# goodthopter10.net
KiCad netlist of a schematic drawn in EAGLE
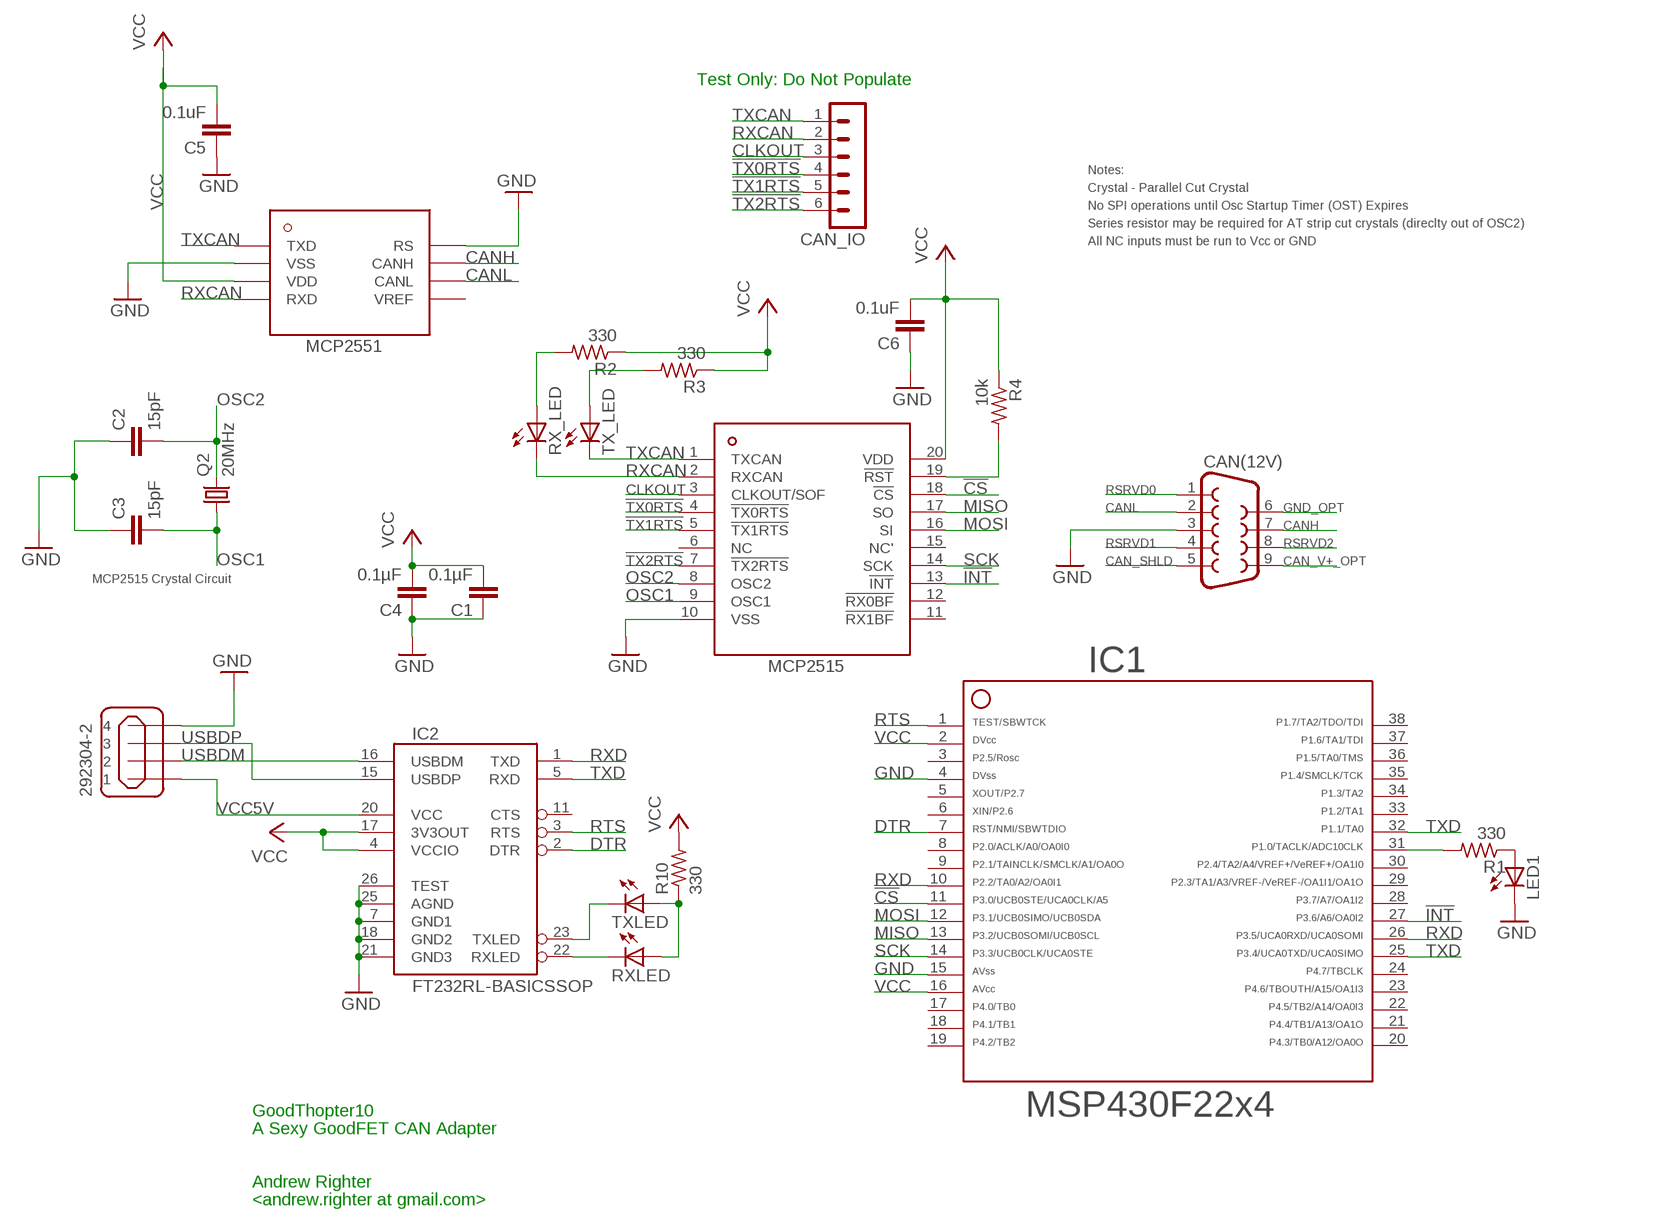
[diagram p0: schematic, sheet 1]

(export (version "E")
  (design (tool "Eeschema 10.0.6"))
  (components
    (comp (ref "292304-2")
      (value "MINI-USB_4P-292304-2")
      (footprint "eagle-import:85-32004-10X")
      (libsource (lib "eagle-import") (part "MINI-USB_4P-292304-2"))
    )
    (comp (ref "C1")
      (value "0.1µF")
      (footprint "eagle-import:C0603")
      (libsource (lib "eagle-import") (part "C-EUC0603"))
    )
    (comp (ref "C2")
      (value "15pF")
      (footprint "eagle-import:C0603")
      (libsource (lib "eagle-import") (part "C-EUC0603"))
    )
    (comp (ref "C3")
      (value "15pF")
      (footprint "eagle-import:C0603")
      (libsource (lib "eagle-import") (part "C-EUC0603"))
    )
    (comp (ref "C4")
      (value "0.1µF")
      (footprint "eagle-import:C0603")
      (libsource (lib "eagle-import") (part "C-EUC0603"))
    )
    (comp (ref "C5")
      (value "0.1uF")
      (footprint "eagle-import:C0603")
      (libsource (lib "eagle-import") (part "C-EUC0603"))
    )
    (comp (ref "C6")
      (value "0.1uF")
      (footprint "eagle-import:C0603")
      (libsource (lib "eagle-import") (part "C-EUC0603"))
    )
    (comp (ref "CAN(12V)")
      (value "DB9MALE")
      (footprint "eagle-import:DB9_MALE")
      (libsource (lib "eagle-import") (part "DB9MALE"))
    )
    (comp (ref "CAN_IO")
      (value "MA06-1")
      (footprint "eagle-import:MA06-1")
      (libsource (lib "eagle-import") (part "MA06-1"))
    )
    (comp (ref "IC1")
      (value "F22X4---DA38")
      (footprint "eagle-import:DA38")
      (libsource (lib "eagle-import") (part "F22X4---DA38"))
    )
    (comp (ref "IC2")
      (value "FT232RL-BASICSSOP")
      (footprint "eagle-import:SSOP28DB")
      (libsource (lib "eagle-import") (part "FT232RL-BASICSSOP"))
    )
    (comp (ref "LED1")
      (value "LEDCHIP-LED0603")
      (footprint "eagle-import:CHIP-LED0603")
      (libsource (lib "eagle-import") (part "LEDCHIP-LED0603"))
    )
    (comp (ref "Q2")
      (value "20MHz")
      (footprint "eagle-import:HC49UP")
      (libsource (lib "eagle-import") (part "CRYSTALHC49UP"))
    )
    (comp (ref "R1")
      (value "330")
      (footprint "eagle-import:R0603")
      (libsource (lib "eagle-import") (part "R-US_R0603"))
    )
    (comp (ref "R2")
      (value "330")
      (footprint "eagle-import:R0603")
      (libsource (lib "eagle-import") (part "R-US_R0603"))
    )
    (comp (ref "R3")
      (value "330")
      (footprint "eagle-import:R0603")
      (libsource (lib "eagle-import") (part "R-US_R0603"))
    )
    (comp (ref "R4")
      (value "10k")
      (footprint "eagle-import:R0603")
      (libsource (lib "eagle-import") (part "R-US_R0603"))
    )
    (comp (ref "R10")
      (value "330")
      (footprint "eagle-import:R0603")
      (libsource (lib "eagle-import") (part "R-US_R0603"))
    )
    (comp (ref "RXLED")
      (value "LEDCHIP-LED0603")
      (footprint "eagle-import:CHIP-LED0603")
      (libsource (lib "eagle-import") (part "LEDCHIP-LED0603"))
    )
    (comp (ref "RX_LED")
      (value "LEDCHIP-LED0603")
      (footprint "eagle-import:CHIP-LED0603")
      (libsource (lib "eagle-import") (part "LEDCHIP-LED0603"))
    )
    (comp (ref "TXLED")
      (value "LEDCHIP-LED0603")
      (footprint "eagle-import:CHIP-LED0603")
      (libsource (lib "eagle-import") (part "LEDCHIP-LED0603"))
    )
    (comp (ref "TX_LED")
      (value "LEDCHIP-LED0603")
      (footprint "eagle-import:CHIP-LED0603")
      (libsource (lib "eagle-import") (part "LEDCHIP-LED0603"))
    )
    (comp (ref "U$1")
      (value "MCP2515")
      (footprint "eagle-import:TSSOP20")
      (libsource (lib "eagle-import") (part "MCP2515"))
    )
    (comp (ref "U$2")
      (value "MCP2551")
      (footprint "eagle-import:SOIC-8")
      (libsource (lib "eagle-import") (part "MCP2551"))
    )
  )
  (nets
    (net (code "1") (name "/CANH") (class "Default")
      (node (ref "CAN(12V)") (pin "7") (pinfunction "7_7") (pintype "passive"))
      (node (ref "U$2") (pin "CANH") (pinfunction "CANH_CANH") (pintype "bidirectional"))
    )
    (net (code "2") (name "/CANL") (class "Default")
      (node (ref "CAN(12V)") (pin "2") (pinfunction "2_2") (pintype "passive"))
      (node (ref "U$2") (pin "CANL") (pinfunction "CANL_CANL") (pintype "bidirectional"))
    )
    (net (code "3") (name "/CAN_SHLD") (class "Default")
      (node (ref "CAN(12V)") (pin "5") (pinfunction "5_5") (pintype "passive"))
    )
    (net (code "4") (name "/CAN_V+_OPT") (class "Default")
      (node (ref "CAN(12V)") (pin "9") (pinfunction "9_9") (pintype "passive"))
    )
    (net (code "5") (name "/CLKOUT") (class "Default")
      (node (ref "CAN_IO") (pin "3") (pinfunction "3_3") (pintype "passive"))
      (node (ref "U$1") (pin "3") (pinfunction "CLKOUT/SOF_3") (pintype "bidirectional"))
    )
    (net (code "6") (name "/DTR") (class "Default")
      (node (ref "IC1") (pin "7") (pinfunction "7_7") (pintype "bidirectional"))
      (node (ref "IC2") (pin "2") (pinfunction "DTR_2") (pintype "bidirectional"))
    )
    (net (code "7") (name "/GND_OPT") (class "Default")
      (node (ref "CAN(12V)") (pin "6") (pinfunction "6_6") (pintype "passive"))
    )
    (net (code "8") (name "/MISO") (class "Default")
      (node (ref "IC1") (pin "13") (pinfunction "13_13") (pintype "bidirectional"))
      (node (ref "U$1") (pin "17") (pinfunction "SO_17") (pintype "bidirectional"))
    )
    (net (code "9") (name "/MOSI") (class "Default")
      (node (ref "IC1") (pin "12") (pinfunction "12_12") (pintype "bidirectional"))
      (node (ref "U$1") (pin "16") (pinfunction "SI_16") (pintype "bidirectional"))
    )
    (net (code "10") (name "/OSC1") (class "Default")
      (node (ref "C3") (pin "2") (pinfunction "2_2") (pintype "passive"))
      (node (ref "Q2") (pin "1") (pinfunction "1_1") (pintype "passive"))
      (node (ref "U$1") (pin "9") (pinfunction "OSC1_9") (pintype "bidirectional"))
    )
    (net (code "11") (name "/OSC2") (class "Default")
      (node (ref "C2") (pin "2") (pinfunction "2_2") (pintype "passive"))
      (node (ref "Q2") (pin "2") (pinfunction "2_2") (pintype "passive"))
      (node (ref "U$1") (pin "8") (pinfunction "OSC2_8") (pintype "bidirectional"))
    )
    (net (code "12") (name "/RSRVD0") (class "Default")
      (node (ref "CAN(12V)") (pin "1") (pinfunction "1_1") (pintype "passive"))
    )
    (net (code "13") (name "/RSRVD1") (class "Default")
      (node (ref "CAN(12V)") (pin "4") (pinfunction "4_4") (pintype "passive"))
    )
    (net (code "14") (name "/RSRVD2") (class "Default")
      (node (ref "CAN(12V)") (pin "8") (pinfunction "8_8") (pintype "passive"))
    )
    (net (code "15") (name "/RTS") (class "Default")
      (node (ref "IC1") (pin "1") (pinfunction "1_1") (pintype "input"))
      (node (ref "IC2") (pin "3") (pinfunction "RTS_3") (pintype "bidirectional"))
    )
    (net (code "16") (name "/RXCAN") (class "Default")
      (node (ref "CAN_IO") (pin "2") (pinfunction "2_2") (pintype "passive"))
      (node (ref "RX_LED") (pin "C") (pinfunction "C_C") (pintype "passive"))
      (node (ref "U$1") (pin "2") (pinfunction "RXCAN_2") (pintype "bidirectional"))
      (node (ref "U$2") (pin "RXD") (pinfunction "RXD_RXD") (pintype "bidirectional"))
    )
    (net (code "17") (name "/RXD") (class "Default")
      (node (ref "IC1") (pin "10") (pinfunction "10_10") (pintype "bidirectional"))
      (node (ref "IC1") (pin "26") (pinfunction "26_26") (pintype "bidirectional"))
      (node (ref "IC2") (pin "1") (pinfunction "TXD_1") (pintype "output"))
    )
    (net (code "18") (name "/SCK") (class "Default")
      (node (ref "IC1") (pin "14") (pinfunction "14_14") (pintype "bidirectional"))
      (node (ref "U$1") (pin "14") (pinfunction "SCK_14") (pintype "bidirectional"))
    )
    (net (code "19") (name "/TXCAN") (class "Default")
      (node (ref "CAN_IO") (pin "1") (pinfunction "1_1") (pintype "passive"))
      (node (ref "TX_LED") (pin "C") (pinfunction "C_C") (pintype "passive"))
      (node (ref "U$1") (pin "1") (pinfunction "TXCAN_1") (pintype "bidirectional"))
      (node (ref "U$2") (pin "TXD") (pinfunction "TXD_TXD") (pintype "bidirectional"))
    )
    (net (code "20") (name "/TXD") (class "Default")
      (node (ref "IC1") (pin "25") (pinfunction "25_25") (pintype "bidirectional"))
      (node (ref "IC1") (pin "32") (pinfunction "32_32") (pintype "bidirectional"))
      (node (ref "IC2") (pin "5") (pinfunction "RXD_5") (pintype "input"))
    )
    (net (code "21") (name "/USBDM") (class "Default")
      (node (ref "292304-2") (pin "2") (pinfunction "2_2") (pintype "passive"))
      (node (ref "IC2") (pin "16") (pinfunction "USBDM_16") (pintype "bidirectional"))
    )
    (net (code "22") (name "/USBDP") (class "Default")
      (node (ref "292304-2") (pin "3") (pinfunction "3_3") (pintype "passive"))
      (node (ref "IC2") (pin "15") (pinfunction "USBDP_15") (pintype "bidirectional"))
    )
    (net (code "23") (name "/VCC5V") (class "Default")
      (node (ref "292304-2") (pin "1") (pinfunction "1_1") (pintype "passive"))
      (node (ref "IC2") (pin "20") (pinfunction "VCC_20") (pintype "power_in"))
    )
    (net (code "24") (name "/~{CS}") (class "Default")
      (node (ref "IC1") (pin "11") (pinfunction "11_11") (pintype "bidirectional"))
      (node (ref "U$1") (pin "18") (pinfunction "~{CS}_18") (pintype "bidirectional"))
    )
    (net (code "25") (name "/~{INT}") (class "Default")
      (node (ref "IC1") (pin "27") (pinfunction "27_27") (pintype "bidirectional"))
      (node (ref "U$1") (pin "13") (pinfunction "~{INT}_13") (pintype "bidirectional"))
    )
    (net (code "26") (name "/~{TX0RTS}") (class "Default")
      (node (ref "CAN_IO") (pin "4") (pinfunction "4_4") (pintype "passive"))
      (node (ref "U$1") (pin "4") (pinfunction "~{TX0RTS}_4") (pintype "bidirectional"))
    )
    (net (code "27") (name "/~{TX1RTS}") (class "Default")
      (node (ref "CAN_IO") (pin "5") (pinfunction "5_5") (pintype "passive"))
      (node (ref "U$1") (pin "5") (pinfunction "~{TX1RTS}_5") (pintype "bidirectional"))
    )
    (net (code "28") (name "/~{TX2RTS}") (class "Default")
      (node (ref "CAN_IO") (pin "6") (pinfunction "6_6") (pintype "passive"))
      (node (ref "U$1") (pin "7") (pinfunction "~{TX2RTS}_7") (pintype "bidirectional"))
    )
    (net (code "29") (name "GND") (class "Default")
      (node (ref "292304-2") (pin "4") (pinfunction "4_4") (pintype "passive"))
      (node (ref "C1") (pin "1") (pinfunction "1_1") (pintype "passive"))
      (node (ref "C2") (pin "1") (pinfunction "1_1") (pintype "passive"))
      (node (ref "C3") (pin "1") (pinfunction "1_1") (pintype "passive"))
      (node (ref "C4") (pin "1") (pinfunction "1_1") (pintype "passive"))
      (node (ref "C5") (pin "1") (pinfunction "1_1") (pintype "passive"))
      (node (ref "C6") (pin "1") (pinfunction "1_1") (pintype "passive"))
      (node (ref "CAN(12V)") (pin "3") (pinfunction "3_3") (pintype "passive"))
      (node (ref "IC1") (pin "15") (pinfunction "15_15") (pintype "power_in"))
      (node (ref "IC1") (pin "4") (pinfunction "4_4") (pintype "power_in"))
      (node (ref "IC2") (pin "18") (pinfunction "GND2_18") (pintype "power_in"))
      (node (ref "IC2") (pin "21") (pinfunction "GND3_21") (pintype "power_in"))
      (node (ref "IC2") (pin "25") (pinfunction "AGND_25") (pintype "power_in"))
      (node (ref "IC2") (pin "26") (pinfunction "TEST_26") (pintype "input"))
      (node (ref "IC2") (pin "7") (pinfunction "GND1_7") (pintype "power_in"))
      (node (ref "LED1") (pin "C") (pinfunction "C_C") (pintype "passive"))
      (node (ref "U$1") (pin "10") (pinfunction "VSS_10") (pintype "bidirectional"))
      (node (ref "U$2") (pin "RS") (pinfunction "RS_RS") (pintype "bidirectional"))
      (node (ref "U$2") (pin "VSS") (pinfunction "VSS_VSS") (pintype "bidirectional"))
    )
    (net (code "30") (name "Net-(IC1-Pad31)") (class "Default")
      (node (ref "IC1") (pin "31") (pinfunction "31_31") (pintype "bidirectional"))
      (node (ref "R1") (pin "2") (pinfunction "2_2") (pintype "passive"))
    )
    (net (code "31") (name "Net-(IC2-RXLED)") (class "Default")
      (node (ref "IC2") (pin "22") (pinfunction "RXLED_22") (pintype "bidirectional"))
      (node (ref "RXLED") (pin "C") (pinfunction "C_C") (pintype "passive"))
    )
    (net (code "32") (name "Net-(IC2-TXLED)") (class "Default")
      (node (ref "IC2") (pin "23") (pinfunction "TXLED_23") (pintype "bidirectional"))
      (node (ref "TXLED") (pin "C") (pinfunction "C_C") (pintype "passive"))
    )
    (net (code "33") (name "Net-(LED1-PadA)") (class "Default")
      (node (ref "LED1") (pin "A") (pinfunction "A_A") (pintype "passive"))
      (node (ref "R1") (pin "1") (pinfunction "1_1") (pintype "passive"))
    )
    (net (code "34") (name "Net-(R2-Pad2)") (class "Default")
      (node (ref "R2") (pin "2") (pinfunction "2_2") (pintype "passive"))
      (node (ref "RX_LED") (pin "A") (pinfunction "A_A") (pintype "passive"))
    )
    (net (code "35") (name "Net-(R3-Pad2)") (class "Default")
      (node (ref "R3") (pin "2") (pinfunction "2_2") (pintype "passive"))
      (node (ref "TX_LED") (pin "A") (pinfunction "A_A") (pintype "passive"))
    )
    (net (code "36") (name "Net-(R10-Pad1)") (class "Default")
      (node (ref "R10") (pin "1") (pinfunction "1_1") (pintype "passive"))
      (node (ref "RXLED") (pin "A") (pinfunction "A_A") (pintype "passive"))
      (node (ref "TXLED") (pin "A") (pinfunction "A_A") (pintype "passive"))
    )
    (net (code "37") (name "Net-(U$1-~{RST})") (class "Default")
      (node (ref "R4") (pin "2") (pinfunction "2_2") (pintype "passive"))
      (node (ref "U$1") (pin "19") (pinfunction "~{RST}_19") (pintype "bidirectional"))
    )
    (net (code "38") (name "VCC") (class "Default")
      (node (ref "C1") (pin "2") (pinfunction "2_2") (pintype "passive"))
      (node (ref "C4") (pin "2") (pinfunction "2_2") (pintype "passive"))
      (node (ref "C5") (pin "2") (pinfunction "2_2") (pintype "passive"))
      (node (ref "C6") (pin "2") (pinfunction "2_2") (pintype "passive"))
      (node (ref "IC1") (pin "16") (pinfunction "16_16") (pintype "power_in"))
      (node (ref "IC1") (pin "2") (pinfunction "2_2") (pintype "power_in"))
      (node (ref "IC2") (pin "17") (pinfunction "3V3OUT_17") (pintype "output"))
      (node (ref "IC2") (pin "4") (pinfunction "VCCIO_4") (pintype "power_in"))
      (node (ref "R10") (pin "2") (pinfunction "2_2") (pintype "passive"))
      (node (ref "R2") (pin "1") (pinfunction "1_1") (pintype "passive"))
      (node (ref "R3") (pin "1") (pinfunction "1_1") (pintype "passive"))
      (node (ref "R4") (pin "1") (pinfunction "1_1") (pintype "passive"))
      (node (ref "U$1") (pin "20") (pinfunction "VDD_20") (pintype "bidirectional"))
      (node (ref "U$2") (pin "VDD") (pinfunction "VDD_VDD") (pintype "bidirectional"))
    )
    (net (code "39") (name "unconnected-(IC1-Pad3)") (class "Default")
      (node (ref "IC1") (pin "3") (pinfunction "3_3") (pintype "bidirectional"))
    )
    (net (code "40") (name "unconnected-(IC1-Pad5)") (class "Default")
      (node (ref "IC1") (pin "5") (pinfunction "5_5") (pintype "bidirectional"))
    )
    (net (code "41") (name "unconnected-(IC1-Pad6)") (class "Default")
      (node (ref "IC1") (pin "6") (pinfunction "6_6") (pintype "bidirectional"))
    )
    (net (code "42") (name "unconnected-(IC1-Pad8)") (class "Default")
      (node (ref "IC1") (pin "8") (pinfunction "8_8") (pintype "bidirectional"))
    )
    (net (code "43") (name "unconnected-(IC1-Pad9)") (class "Default")
      (node (ref "IC1") (pin "9") (pinfunction "9_9") (pintype "bidirectional"))
    )
    (net (code "44") (name "unconnected-(IC1-Pad17)") (class "Default")
      (node (ref "IC1") (pin "17") (pinfunction "17_17") (pintype "bidirectional"))
    )
    (net (code "45") (name "unconnected-(IC1-Pad18)") (class "Default")
      (node (ref "IC1") (pin "18") (pinfunction "18_18") (pintype "bidirectional"))
    )
    (net (code "46") (name "unconnected-(IC1-Pad19)") (class "Default")
      (node (ref "IC1") (pin "19") (pinfunction "19_19") (pintype "bidirectional"))
    )
    (net (code "47") (name "unconnected-(IC1-Pad20)") (class "Default")
      (node (ref "IC1") (pin "20") (pinfunction "20_20") (pintype "bidirectional"))
    )
    (net (code "48") (name "unconnected-(IC1-Pad21)") (class "Default")
      (node (ref "IC1") (pin "21") (pinfunction "21_21") (pintype "bidirectional"))
    )
    (net (code "49") (name "unconnected-(IC1-Pad22)") (class "Default")
      (node (ref "IC1") (pin "22") (pinfunction "22_22") (pintype "bidirectional"))
    )
    (net (code "50") (name "unconnected-(IC1-Pad23)") (class "Default")
      (node (ref "IC1") (pin "23") (pinfunction "23_23") (pintype "bidirectional"))
    )
    (net (code "51") (name "unconnected-(IC1-Pad24)") (class "Default")
      (node (ref "IC1") (pin "24") (pinfunction "24_24") (pintype "bidirectional"))
    )
    (net (code "52") (name "unconnected-(IC1-Pad28)") (class "Default")
      (node (ref "IC1") (pin "28") (pinfunction "28_28") (pintype "bidirectional"))
    )
    (net (code "53") (name "unconnected-(IC1-Pad29)") (class "Default")
      (node (ref "IC1") (pin "29") (pinfunction "29_29") (pintype "bidirectional"))
    )
    (net (code "54") (name "unconnected-(IC1-Pad30)") (class "Default")
      (node (ref "IC1") (pin "30") (pinfunction "30_30") (pintype "bidirectional"))
    )
    (net (code "55") (name "unconnected-(IC1-Pad33)") (class "Default")
      (node (ref "IC1") (pin "33") (pinfunction "33_33") (pintype "bidirectional"))
    )
    (net (code "56") (name "unconnected-(IC1-Pad34)") (class "Default")
      (node (ref "IC1") (pin "34") (pinfunction "34_34") (pintype "bidirectional"))
    )
    (net (code "57") (name "unconnected-(IC1-Pad35)") (class "Default")
      (node (ref "IC1") (pin "35") (pinfunction "35_35") (pintype "bidirectional"))
    )
    (net (code "58") (name "unconnected-(IC1-Pad36)") (class "Default")
      (node (ref "IC1") (pin "36") (pinfunction "36_36") (pintype "bidirectional"))
    )
    (net (code "59") (name "unconnected-(IC1-Pad37)") (class "Default")
      (node (ref "IC1") (pin "37") (pinfunction "37_37") (pintype "bidirectional"))
    )
    (net (code "60") (name "unconnected-(IC1-Pad38)") (class "Default")
      (node (ref "IC1") (pin "38") (pinfunction "38_38") (pintype "bidirectional"))
    )
    (net (code "61") (name "unconnected-(IC2-CTS-Pad11)") (class "Default")
      (node (ref "IC2") (pin "11") (pinfunction "CTS_11") (pintype "bidirectional"))
    )
    (net (code "62") (name "unconnected-(U$1-NC'-Pad15)") (class "Default")
      (node (ref "U$1") (pin "15") (pinfunction "NC'_15") (pintype "bidirectional"))
    )
    (net (code "63") (name "unconnected-(U$1-NC-Pad6)") (class "Default")
      (node (ref "U$1") (pin "6") (pinfunction "NC_6") (pintype "bidirectional"))
    )
    (net (code "64") (name "unconnected-(U$1-~{RX0BF}-Pad12)") (class "Default")
      (node (ref "U$1") (pin "12") (pinfunction "~{RX0BF}_12") (pintype "bidirectional"))
    )
    (net (code "65") (name "unconnected-(U$1-~{RX1BF}-Pad11)") (class "Default")
      (node (ref "U$1") (pin "11") (pinfunction "~{RX1BF}_11") (pintype "bidirectional"))
    )
    (net (code "66") (name "unconnected-(U$2-PadVREF)") (class "Default")
      (node (ref "U$2") (pin "VREF") (pinfunction "VREF_VREF") (pintype "bidirectional"))
    )
  )
)
